# Thumb_throttle_switch_v8.net
KiCad netlist of a schematic drawn in EAGLE
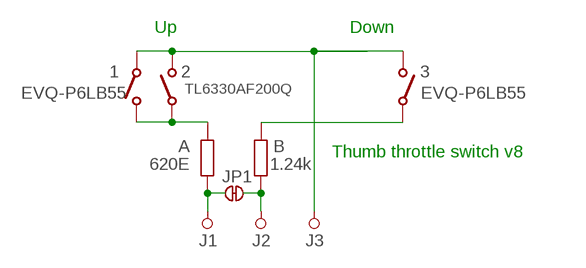
[diagram p0: schematic, sheet 1]

(export (version "E")
  (design (tool "Eeschema 10.0.6"))
  (components
    (comp (ref "1")
      (value "EVQ-P6LB55")
      (footprint "eagle-import:TACTILE_SWITCH_SMD-2")
      (libsource (lib "eagle-import") (part "TACTILE-IP68"))
    )
    (comp (ref "2")
      (value "TL6330AF200Q")
      (footprint "eagle-import:TACTILE_SWITCH_SMD_4.6X2.8MM")
      (libsource (lib "eagle-import") (part "TACTILE4,62,8"))
    )
    (comp (ref "3")
      (value "EVQ-P6LB55")
      (footprint "eagle-import:TACTILE_SWITCH_SMD-2")
      (libsource (lib "eagle-import") (part "TACTILE-IP68"))
    )
    (comp (ref "A")
      (value "620E")
      (footprint "eagle-import:0603")
      (libsource (lib "eagle-import") (part "SMD-R'"))
    )
    (comp (ref "B")
      (value "1.24k")
      (footprint "eagle-import:0603")
      (libsource (lib "eagle-import") (part "SMD-R'"))
    )
    (comp (ref "J1")
      (value "nc")
      (footprint "eagle-import:PIN-0.3MM")
      (libsource (lib "eagle-import") (part "PIN0.3MM"))
    )
    (comp (ref "J2")
      (value "nc")
      (footprint "eagle-import:PIN-0.3MM")
      (libsource (lib "eagle-import") (part "PIN0.3MM"))
    )
    (comp (ref "J3")
      (value "nc")
      (footprint "eagle-import:PIN-0.3MM")
      (libsource (lib "eagle-import") (part "PIN0.3MM"))
    )
    (comp (ref "JP1")
      (value "nc")
      (footprint "eagle-import:JUMPER_NC")
      (libsource (lib "eagle-import") (part "JUMPER_SJ_NCNC"))
    )
  )
  (nets
    (net (code "1") (name "Net-(1-O)") (class "Default")
      (node (ref "1") (pin "1") (pinfunction "O_1") (pintype "passive"))
      (node (ref "2") (pin "2") (pinfunction "P_2") (pintype "passive"))
      (node (ref "2") (pin "3") (pinfunction "P_3") (pintype "passive"))
      (node (ref "A") (pin "2") (pinfunction "2_2") (pintype "passive"))
    )
    (net (code "2") (name "Net-(1-P)") (class "Default")
      (node (ref "1") (pin "2") (pinfunction "P_2") (pintype "passive"))
      (node (ref "2") (pin "1") (pinfunction "O_1") (pintype "passive"))
      (node (ref "2") (pin "4") (pinfunction "O_4") (pintype "passive"))
      (node (ref "3") (pin "1") (pinfunction "O_1") (pintype "passive"))
      (node (ref "J3") (pin "1") (pinfunction "1_1") (pintype "passive"))
    )
    (net (code "3") (name "Net-(3-P)") (class "Default")
      (node (ref "3") (pin "2") (pinfunction "P_2") (pintype "passive"))
      (node (ref "B") (pin "2") (pinfunction "2_2") (pintype "passive"))
    )
    (net (code "4") (name "Net-(A-Pad1)") (class "Default")
      (node (ref "A") (pin "1") (pinfunction "1_1") (pintype "passive"))
      (node (ref "J1") (pin "1") (pinfunction "1_1") (pintype "passive"))
      (node (ref "JP1") (pin "1") (pinfunction "1_1") (pintype "passive"))
      (node (ref "JP1") (pin "1A") (pinfunction "1_1A") (pintype "passive"))
    )
    (net (code "5") (name "Net-(B-Pad1)") (class "Default")
      (node (ref "B") (pin "1") (pinfunction "1_1") (pintype "passive"))
      (node (ref "J2") (pin "1") (pinfunction "1_1") (pintype "passive"))
      (node (ref "JP1") (pin "2") (pinfunction "2_2") (pintype "passive"))
      (node (ref "JP1") (pin "2B") (pinfunction "2_2B") (pintype "passive"))
    )
  )
)
